# WeatherLight_Router.net
KiCad netlist of a schematic drawn in EAGLE
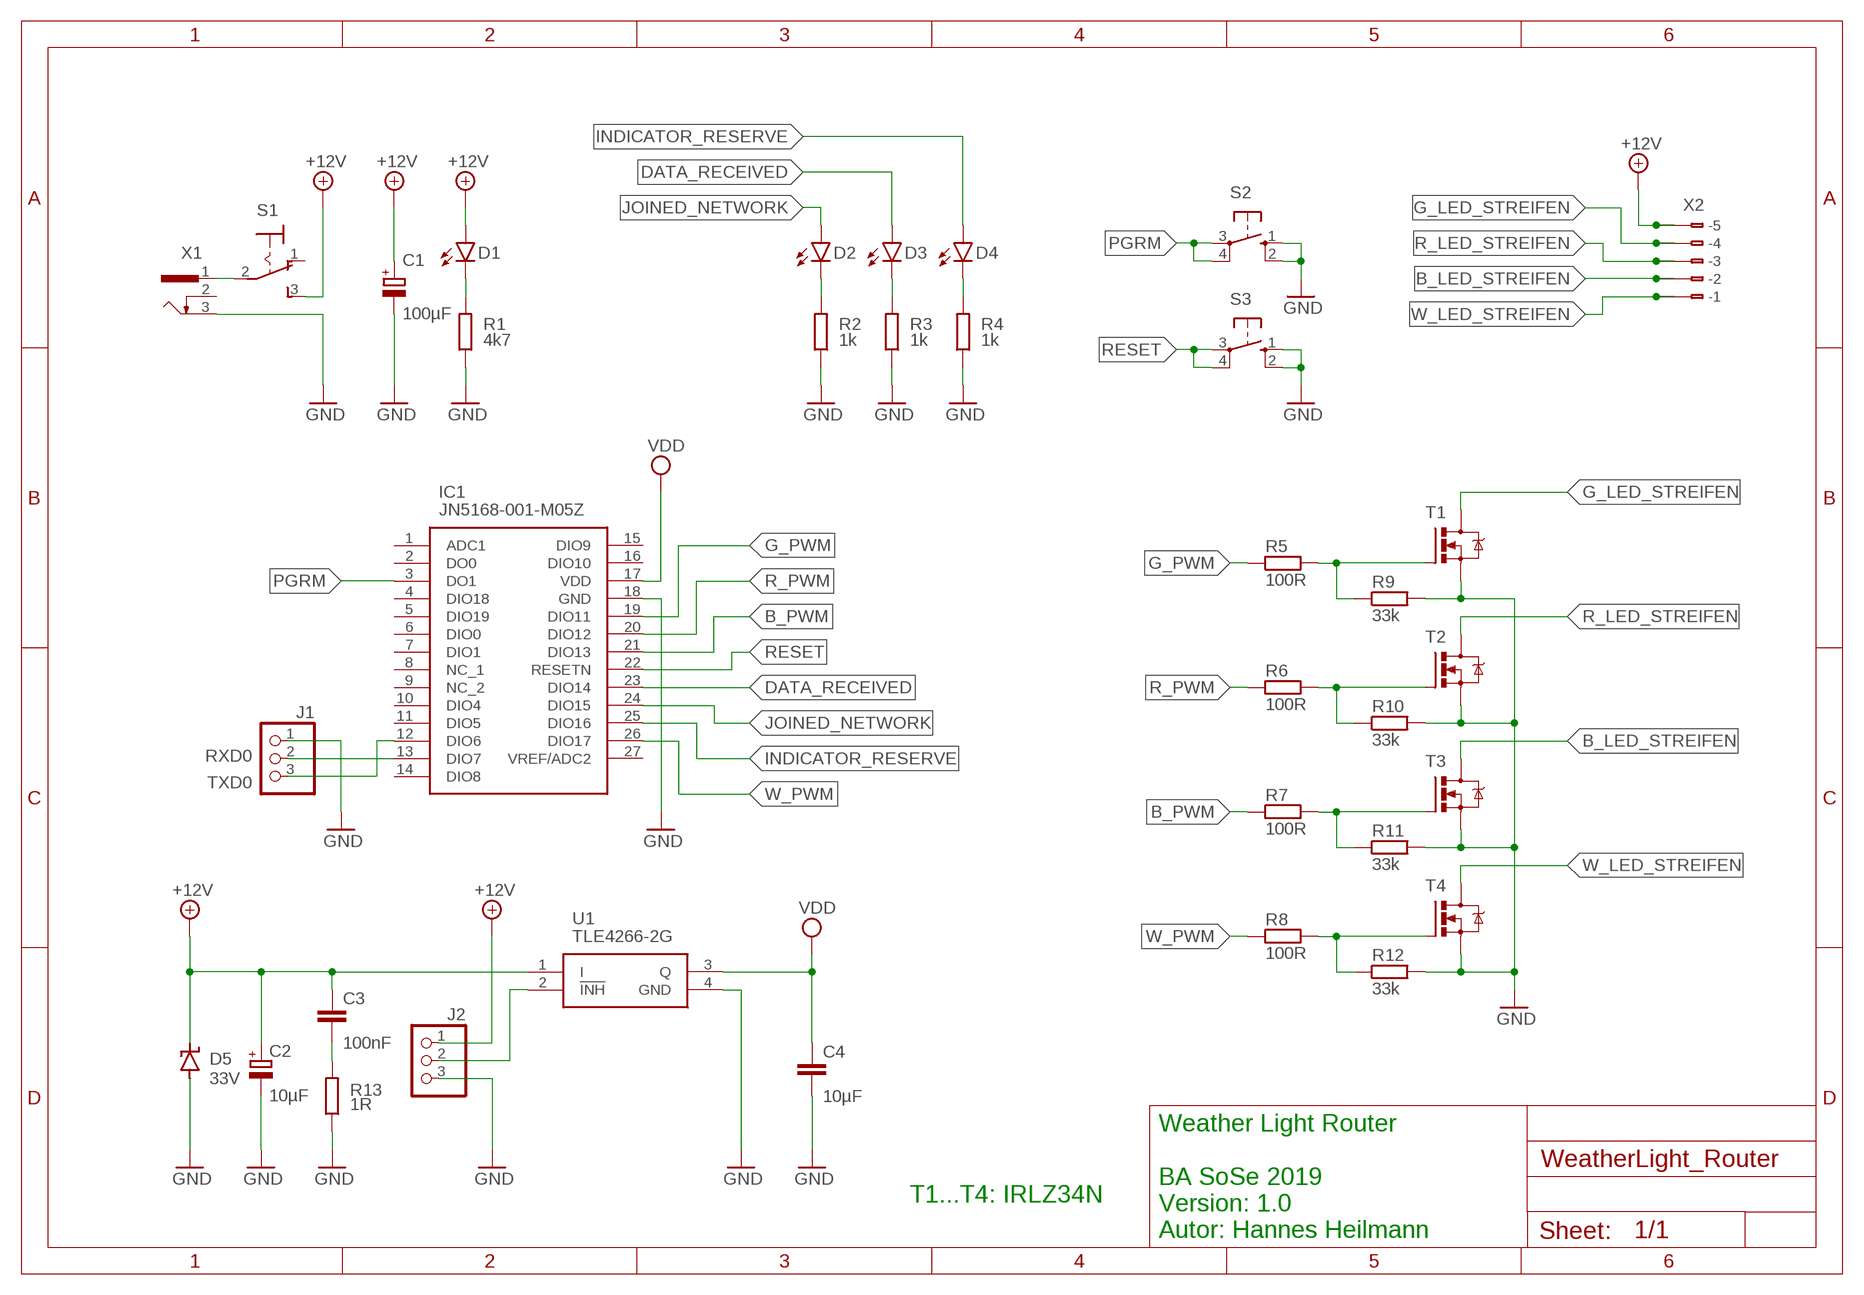
[diagram p0: schematic, sheet 1]

(export (version "E")
  (design (tool "Eeschema 10.0.6"))
  (components
    (comp (ref "C1")
      (value "100µF")
      (footprint "eagle-import:PANASONIC_D")
      (libsource (lib "eagle-import") (part "CPOL-EUD"))
    )
    (comp (ref "C2")
      (value "10µF")
      (footprint "eagle-import:PANASONIC_B")
      (libsource (lib "eagle-import") (part "CPOL-EUB"))
    )
    (comp (ref "C3")
      (value "100nF")
      (footprint "eagle-import:C1206")
      (libsource (lib "eagle-import") (part "C-EUC1206"))
    )
    (comp (ref "C4")
      (value "10µF")
      (footprint "eagle-import:C1206K")
      (libsource (lib "eagle-import") (part "C-EUC1206K"))
    )
    (comp (ref "D1")
      (value "LEDCHIPLED_1206")
      (footprint "eagle-import:CHIPLED_1206")
      (libsource (lib "eagle-import") (part "LEDCHIPLED_1206"))
    )
    (comp (ref "D2")
      (value "LEDCHIPLED_1206")
      (footprint "eagle-import:CHIPLED_1206")
      (libsource (lib "eagle-import") (part "LEDCHIPLED_1206"))
    )
    (comp (ref "D3")
      (value "LEDCHIPLED_1206")
      (footprint "eagle-import:CHIPLED_1206")
      (libsource (lib "eagle-import") (part "LEDCHIPLED_1206"))
    )
    (comp (ref "D4")
      (value "LEDCHIPLED_1206")
      (footprint "eagle-import:CHIPLED_1206")
      (libsource (lib "eagle-import") (part "LEDCHIPLED_1206"))
    )
    (comp (ref "D5")
      (value "33V")
      (footprint "eagle-import:SMBJ")
      (libsource (lib "eagle-import") (part "SUPPRESSOR-SMBJ"))
    )
    (comp (ref "IC1")
      (value "JN5168-001-M05Z")
      (footprint "eagle-import:JN5168001M05Z")
      (fields (field (name "MOUSER_PART_NUMBER") "771-JN5168-001-M05Z"))
      (libsource (lib "eagle-import") (part "JN5168-001-M05Z"))
    )
    (comp (ref "J1")
      (value "PINHD-1X3")
      (footprint "eagle-import:1X03")
      (libsource (lib "eagle-import") (part "PINHD-1X3"))
    )
    (comp (ref "J2")
      (value "PINHD-1X3")
      (footprint "eagle-import:1X03")
      (libsource (lib "eagle-import") (part "PINHD-1X3"))
    )
    (comp (ref "R1")
      (value "4k7")
      (footprint "eagle-import:R1206")
      (libsource (lib "eagle-import") (part "R-EU_R1206"))
    )
    (comp (ref "R2")
      (value "1k")
      (footprint "eagle-import:R1206")
      (libsource (lib "eagle-import") (part "R-EU_R1206"))
    )
    (comp (ref "R3")
      (value "1k")
      (footprint "eagle-import:R1206")
      (libsource (lib "eagle-import") (part "R-EU_R1206"))
    )
    (comp (ref "R4")
      (value "1k")
      (footprint "eagle-import:R1206")
      (libsource (lib "eagle-import") (part "R-EU_R1206"))
    )
    (comp (ref "R5")
      (value "100R")
      (footprint "eagle-import:R1206")
      (libsource (lib "eagle-import") (part "R-EU_R1206"))
    )
    (comp (ref "R6")
      (value "100R")
      (footprint "eagle-import:R1206")
      (libsource (lib "eagle-import") (part "R-EU_R1206"))
    )
    (comp (ref "R7")
      (value "100R")
      (footprint "eagle-import:R1206")
      (libsource (lib "eagle-import") (part "R-EU_R1206"))
    )
    (comp (ref "R8")
      (value "100R")
      (footprint "eagle-import:R1206")
      (libsource (lib "eagle-import") (part "R-EU_R1206"))
    )
    (comp (ref "R9")
      (value "33k")
      (footprint "eagle-import:R1206")
      (libsource (lib "eagle-import") (part "R-EU_R1206"))
    )
    (comp (ref "R10")
      (value "33k")
      (footprint "eagle-import:R1206")
      (libsource (lib "eagle-import") (part "R-EU_R1206"))
    )
    (comp (ref "R11")
      (value "33k")
      (footprint "eagle-import:R1206")
      (libsource (lib "eagle-import") (part "R-EU_R1206"))
    )
    (comp (ref "R12")
      (value "33k")
      (footprint "eagle-import:R1206")
      (libsource (lib "eagle-import") (part "R-EU_R1206"))
    )
    (comp (ref "R13")
      (value "1R")
      (footprint "eagle-import:R1206")
      (libsource (lib "eagle-import") (part "R-EU_R1206"))
    )
    (comp (ref "S1")
      (value "M9040P")
      (footprint "eagle-import:M9040P")
      (libsource (lib "eagle-import") (part "M9040P"))
    )
    (comp (ref "S2")
      (value "10-XX")
      (footprint "eagle-import:B3F-10XX")
      (fields (field (name "MPN") "B3F-1000"))
      (libsource (lib "eagle-import") (part "10-XX"))
    )
    (comp (ref "S3")
      (value "10-XX")
      (footprint "eagle-import:B3F-10XX")
      (fields (field (name "MPN") "B3F-1000"))
      (libsource (lib "eagle-import") (part "10-XX"))
    )
    (comp (ref "T1")
      (value "IRLZ44Z")
      (footprint "eagle-import:TO220BH")
      (libsource (lib "eagle-import") (part "IRLZ44Z"))
    )
    (comp (ref "T2")
      (value "IRLZ44Z")
      (footprint "eagle-import:TO220BH")
      (libsource (lib "eagle-import") (part "IRLZ44Z"))
    )
    (comp (ref "T3")
      (value "IRLZ44Z")
      (footprint "eagle-import:TO220BH")
      (libsource (lib "eagle-import") (part "IRLZ44Z"))
    )
    (comp (ref "T4")
      (value "IRLZ44Z")
      (footprint "eagle-import:TO220BH")
      (libsource (lib "eagle-import") (part "IRLZ44Z"))
    )
    (comp (ref "U1")
      (value "TLE4266-2G")
      (footprint "eagle-import:SOT230P700X170-4N")
      (fields (field (name "MOUSER_PART_NUMBER") "726-TLE42662G"))
      (libsource (lib "eagle-import") (part "TLE4266-2G"))
    )
    (comp (ref "X1")
      (value "NEB21R")
      (footprint "eagle-import:NEB21R")
      (fields (field (name "MPN") "NEB 21 R"))
      (libsource (lib "eagle-import") (part "NEB21R"))
    )
    (comp (ref "X2")
      (value "233-505")
      (footprint "eagle-import:233-505")
      (fields (field (name "MF") "Wago Corporation") (field (name "MPN") "0233-0505"))
      (libsource (lib "eagle-import") (part "233-505"))
    )
  )
  (nets
    (net (code "1") (name "+12V") (class "Default")
      (node (ref "C1") (pin "+") (pinfunction "+_+") (pintype "passive"))
      (node (ref "C2") (pin "+") (pinfunction "+_+") (pintype "passive"))
      (node (ref "C3") (pin "1") (pinfunction "1_1") (pintype "passive"))
      (node (ref "D1") (pin "A") (pinfunction "A_A") (pintype "passive"))
      (node (ref "D5") (pin "C") (pinfunction "C_C") (pintype "passive"))
      (node (ref "J2") (pin "1") (pinfunction "1_1") (pintype "passive"))
      (node (ref "S1") (pin "3") (pinfunction "S_3") (pintype "passive"))
      (node (ref "U1") (pin "1") (pinfunction "I_1") (pintype "bidirectional"))
      (node (ref "X2") (pin "A5") (pinfunction "-5_A5") (pintype "passive"))
      (node (ref "X2") (pin "B5") (pinfunction "B-5_B5") (pintype "passive"))
    )
    (net (code "2") (name "/RXD0") (class "Default")
      (node (ref "IC1") (pin "13") (pinfunction "DIO7_13") (pintype "bidirectional"))
      (node (ref "J1") (pin "2") (pinfunction "2_2") (pintype "passive"))
    )
    (net (code "3") (name "/TXD0") (class "Default")
      (node (ref "IC1") (pin "12") (pinfunction "DIO6_12") (pintype "bidirectional"))
      (node (ref "J1") (pin "3") (pinfunction "3_3") (pintype "passive"))
    )
    (net (code "4") (name "B_LED_STREIFEN") (class "Default")
      (node (ref "T3") (pin "D") (pinfunction "D_D") (pintype "passive"))
      (node (ref "X2") (pin "A2") (pinfunction "-2_A2") (pintype "passive"))
      (node (ref "X2") (pin "B2") (pinfunction "B-2_B2") (pintype "passive"))
    )
    (net (code "5") (name "B_PWM") (class "Default")
      (node (ref "IC1") (pin "21") (pinfunction "DIO13_21") (pintype "bidirectional"))
      (node (ref "R7") (pin "1") (pinfunction "1_1") (pintype "passive"))
    )
    (net (code "6") (name "DATA_RECEIVED") (class "Default")
      (node (ref "D3") (pin "A") (pinfunction "A_A") (pintype "passive"))
      (node (ref "IC1") (pin "23") (pinfunction "DIO14_23") (pintype "bidirectional"))
    )
    (net (code "7") (name "GND") (class "Default")
      (node (ref "C1") (pin "-") (pinfunction "-_-") (pintype "passive"))
      (node (ref "C2") (pin "-") (pinfunction "-_-") (pintype "passive"))
      (node (ref "C4") (pin "2") (pinfunction "2_2") (pintype "passive"))
      (node (ref "D5") (pin "A") (pinfunction "A_A") (pintype "passive"))
      (node (ref "IC1") (pin "18") (pinfunction "GND_18") (pintype "bidirectional"))
      (node (ref "J1") (pin "1") (pinfunction "1_1") (pintype "passive"))
      (node (ref "J2") (pin "3") (pinfunction "3_3") (pintype "passive"))
      (node (ref "R1") (pin "1") (pinfunction "1_1") (pintype "passive"))
      (node (ref "R10") (pin "2") (pinfunction "2_2") (pintype "passive"))
      (node (ref "R11") (pin "2") (pinfunction "2_2") (pintype "passive"))
      (node (ref "R12") (pin "2") (pinfunction "2_2") (pintype "passive"))
      (node (ref "R13") (pin "1") (pinfunction "1_1") (pintype "passive"))
      (node (ref "R2") (pin "1") (pinfunction "1_1") (pintype "passive"))
      (node (ref "R3") (pin "1") (pinfunction "1_1") (pintype "passive"))
      (node (ref "R4") (pin "1") (pinfunction "1_1") (pintype "passive"))
      (node (ref "R9") (pin "2") (pinfunction "2_2") (pintype "passive"))
      (node (ref "S2") (pin "1") (pinfunction "S_1") (pintype "passive"))
      (node (ref "S2") (pin "2") (pinfunction "S1_2") (pintype "passive"))
      (node (ref "S3") (pin "1") (pinfunction "S_1") (pintype "passive"))
      (node (ref "S3") (pin "2") (pinfunction "S1_2") (pintype "passive"))
      (node (ref "T1") (pin "S") (pinfunction "S_S") (pintype "passive"))
      (node (ref "T2") (pin "S") (pinfunction "S_S") (pintype "passive"))
      (node (ref "T3") (pin "S") (pinfunction "S_S") (pintype "passive"))
      (node (ref "T4") (pin "S") (pinfunction "S_S") (pintype "passive"))
      (node (ref "U1") (pin "4") (pinfunction "GND_4") (pintype "bidirectional"))
      (node (ref "X1") (pin "3") (pinfunction "3_3") (pintype "passive"))
    )
    (net (code "8") (name "G_LED_STREIFEN") (class "Default")
      (node (ref "T1") (pin "D") (pinfunction "D_D") (pintype "passive"))
      (node (ref "X2") (pin "A4") (pinfunction "-4_A4") (pintype "passive"))
      (node (ref "X2") (pin "B4") (pinfunction "B-4_B4") (pintype "passive"))
    )
    (net (code "9") (name "G_PWM") (class "Default")
      (node (ref "IC1") (pin "19") (pinfunction "DIO11_19") (pintype "bidirectional"))
      (node (ref "R5") (pin "1") (pinfunction "1_1") (pintype "passive"))
    )
    (net (code "10") (name "INDICATOR_RESERVE") (class "Default")
      (node (ref "D4") (pin "A") (pinfunction "A_A") (pintype "passive"))
      (node (ref "IC1") (pin "25") (pinfunction "DIO16_25") (pintype "bidirectional"))
    )
    (net (code "11") (name "JOINED_NETWORK") (class "Default")
      (node (ref "D2") (pin "A") (pinfunction "A_A") (pintype "passive"))
      (node (ref "IC1") (pin "24") (pinfunction "DIO15_24") (pintype "bidirectional"))
    )
    (net (code "12") (name "Net-(C3-Pad2)") (class "Default")
      (node (ref "C3") (pin "2") (pinfunction "2_2") (pintype "passive"))
      (node (ref "R13") (pin "2") (pinfunction "2_2") (pintype "passive"))
    )
    (net (code "13") (name "Net-(D1-PadC)") (class "Default")
      (node (ref "D1") (pin "C") (pinfunction "C_C") (pintype "passive"))
      (node (ref "R1") (pin "2") (pinfunction "2_2") (pintype "passive"))
    )
    (net (code "14") (name "Net-(D2-PadC)") (class "Default")
      (node (ref "D2") (pin "C") (pinfunction "C_C") (pintype "passive"))
      (node (ref "R2") (pin "2") (pinfunction "2_2") (pintype "passive"))
    )
    (net (code "15") (name "Net-(D3-PadC)") (class "Default")
      (node (ref "D3") (pin "C") (pinfunction "C_C") (pintype "passive"))
      (node (ref "R3") (pin "2") (pinfunction "2_2") (pintype "passive"))
    )
    (net (code "16") (name "Net-(D4-PadC)") (class "Default")
      (node (ref "D4") (pin "C") (pinfunction "C_C") (pintype "passive"))
      (node (ref "R4") (pin "2") (pinfunction "2_2") (pintype "passive"))
    )
    (net (code "17") (name "Net-(R5-Pad2)") (class "Default")
      (node (ref "R5") (pin "2") (pinfunction "2_2") (pintype "passive"))
      (node (ref "R9") (pin "1") (pinfunction "1_1") (pintype "passive"))
      (node (ref "T1") (pin "G") (pinfunction "G_G") (pintype "passive"))
    )
    (net (code "18") (name "Net-(R10-Pad1)") (class "Default")
      (node (ref "R10") (pin "1") (pinfunction "1_1") (pintype "passive"))
      (node (ref "R6") (pin "2") (pinfunction "2_2") (pintype "passive"))
      (node (ref "T2") (pin "G") (pinfunction "G_G") (pintype "passive"))
    )
    (net (code "19") (name "Net-(R11-Pad1)") (class "Default")
      (node (ref "R11") (pin "1") (pinfunction "1_1") (pintype "passive"))
      (node (ref "R7") (pin "2") (pinfunction "2_2") (pintype "passive"))
      (node (ref "T3") (pin "G") (pinfunction "G_G") (pintype "passive"))
    )
    (net (code "20") (name "Net-(R12-Pad1)") (class "Default")
      (node (ref "R12") (pin "1") (pinfunction "1_1") (pintype "passive"))
      (node (ref "R8") (pin "2") (pinfunction "2_2") (pintype "passive"))
      (node (ref "T4") (pin "G") (pinfunction "G_G") (pintype "passive"))
    )
    (net (code "21") (name "Net-(S1-P)") (class "Default")
      (node (ref "S1") (pin "2") (pinfunction "P_2") (pintype "passive"))
      (node (ref "X1") (pin "1") (pinfunction "1_1") (pintype "passive"))
    )
    (net (code "22") (name "Net-(U1-~{INH})") (class "Default")
      (node (ref "J2") (pin "2") (pinfunction "2_2") (pintype "passive"))
      (node (ref "U1") (pin "2") (pinfunction "~{INH}_2") (pintype "bidirectional"))
    )
    (net (code "23") (name "PGRM") (class "Default")
      (node (ref "IC1") (pin "3") (pinfunction "DO1_3") (pintype "bidirectional"))
      (node (ref "S2") (pin "3") (pinfunction "P_3") (pintype "passive"))
      (node (ref "S2") (pin "4") (pinfunction "P1_4") (pintype "passive"))
    )
    (net (code "24") (name "RESET") (class "Default")
      (node (ref "IC1") (pin "22") (pinfunction "RESETN_22") (pintype "bidirectional"))
      (node (ref "S3") (pin "3") (pinfunction "P_3") (pintype "passive"))
      (node (ref "S3") (pin "4") (pinfunction "P1_4") (pintype "passive"))
    )
    (net (code "25") (name "R_LED_STREIFEN") (class "Default")
      (node (ref "T2") (pin "D") (pinfunction "D_D") (pintype "passive"))
      (node (ref "X2") (pin "A3") (pinfunction "-3_A3") (pintype "passive"))
      (node (ref "X2") (pin "B3") (pinfunction "B-3_B3") (pintype "passive"))
    )
    (net (code "26") (name "R_PWM") (class "Default")
      (node (ref "IC1") (pin "20") (pinfunction "DIO12_20") (pintype "bidirectional"))
      (node (ref "R6") (pin "1") (pinfunction "1_1") (pintype "passive"))
    )
    (net (code "27") (name "VDD") (class "Default")
      (node (ref "C4") (pin "1") (pinfunction "1_1") (pintype "passive"))
      (node (ref "IC1") (pin "17") (pinfunction "VDD_17") (pintype "bidirectional"))
      (node (ref "U1") (pin "3") (pinfunction "Q_3") (pintype "bidirectional"))
    )
    (net (code "28") (name "W_LED_STREIFEN") (class "Default")
      (node (ref "T4") (pin "D") (pinfunction "D_D") (pintype "passive"))
      (node (ref "X2") (pin "A1") (pinfunction "-1_A1") (pintype "passive"))
      (node (ref "X2") (pin "B1") (pinfunction "B-1_B1") (pintype "passive"))
    )
    (net (code "29") (name "W_PWM") (class "Default")
      (node (ref "IC1") (pin "26") (pinfunction "DIO17_26") (pintype "bidirectional"))
      (node (ref "R8") (pin "1") (pinfunction "1_1") (pintype "passive"))
    )
    (net (code "30") (name "unconnected-(IC1-ADC1-Pad1)") (class "Default")
      (node (ref "IC1") (pin "1") (pinfunction "ADC1_1") (pintype "bidirectional"))
    )
    (net (code "31") (name "unconnected-(IC1-DIO0-Pad6)") (class "Default")
      (node (ref "IC1") (pin "6") (pinfunction "DIO0_6") (pintype "bidirectional"))
    )
    (net (code "32") (name "unconnected-(IC1-DIO1-Pad7)") (class "Default")
      (node (ref "IC1") (pin "7") (pinfunction "DIO1_7") (pintype "bidirectional"))
    )
    (net (code "33") (name "unconnected-(IC1-DIO4-Pad10)") (class "Default")
      (node (ref "IC1") (pin "10") (pinfunction "DIO4_10") (pintype "bidirectional"))
    )
    (net (code "34") (name "unconnected-(IC1-DIO5-Pad11)") (class "Default")
      (node (ref "IC1") (pin "11") (pinfunction "DIO5_11") (pintype "bidirectional"))
    )
    (net (code "35") (name "unconnected-(IC1-DIO8-Pad14)") (class "Default")
      (node (ref "IC1") (pin "14") (pinfunction "DIO8_14") (pintype "bidirectional"))
    )
    (net (code "36") (name "unconnected-(IC1-DIO9-Pad15)") (class "Default")
      (node (ref "IC1") (pin "15") (pinfunction "DIO9_15") (pintype "bidirectional"))
    )
    (net (code "37") (name "unconnected-(IC1-DIO10-Pad16)") (class "Default")
      (node (ref "IC1") (pin "16") (pinfunction "DIO10_16") (pintype "bidirectional"))
    )
    (net (code "38") (name "unconnected-(IC1-DIO18-Pad4)") (class "Default")
      (node (ref "IC1") (pin "4") (pinfunction "DIO18_4") (pintype "bidirectional"))
    )
    (net (code "39") (name "unconnected-(IC1-DIO19-Pad5)") (class "Default")
      (node (ref "IC1") (pin "5") (pinfunction "DIO19_5") (pintype "bidirectional"))
    )
    (net (code "40") (name "unconnected-(IC1-DO0-Pad2)") (class "Default")
      (node (ref "IC1") (pin "2") (pinfunction "DO0_2") (pintype "bidirectional"))
    )
    (net (code "41") (name "unconnected-(IC1-NC_1-Pad8)") (class "Default")
      (node (ref "IC1") (pin "8") (pinfunction "NC_1_8") (pintype "bidirectional"))
    )
    (net (code "42") (name "unconnected-(IC1-NC_2-Pad9)") (class "Default")
      (node (ref "IC1") (pin "9") (pinfunction "NC_2_9") (pintype "bidirectional"))
    )
    (net (code "43") (name "unconnected-(IC1-VREF{slash}ADC2-Pad27)") (class "Default")
      (node (ref "IC1") (pin "27") (pinfunction "VREF/ADC2_27") (pintype "bidirectional"))
    )
    (net (code "44") (name "unconnected-(S1-O-Pad1)") (class "Default")
      (node (ref "S1") (pin "1") (pinfunction "O_1") (pintype "passive"))
    )
    (net (code "45") (name "unconnected-(X1-Pad2)") (class "Default")
      (node (ref "X1") (pin "2") (pinfunction "2_2") (pintype "passive"))
    )
  )
)
